# SCH_urmom_2025-01-09.net
KiCad netlist of a schematic drawn in EasyEDA
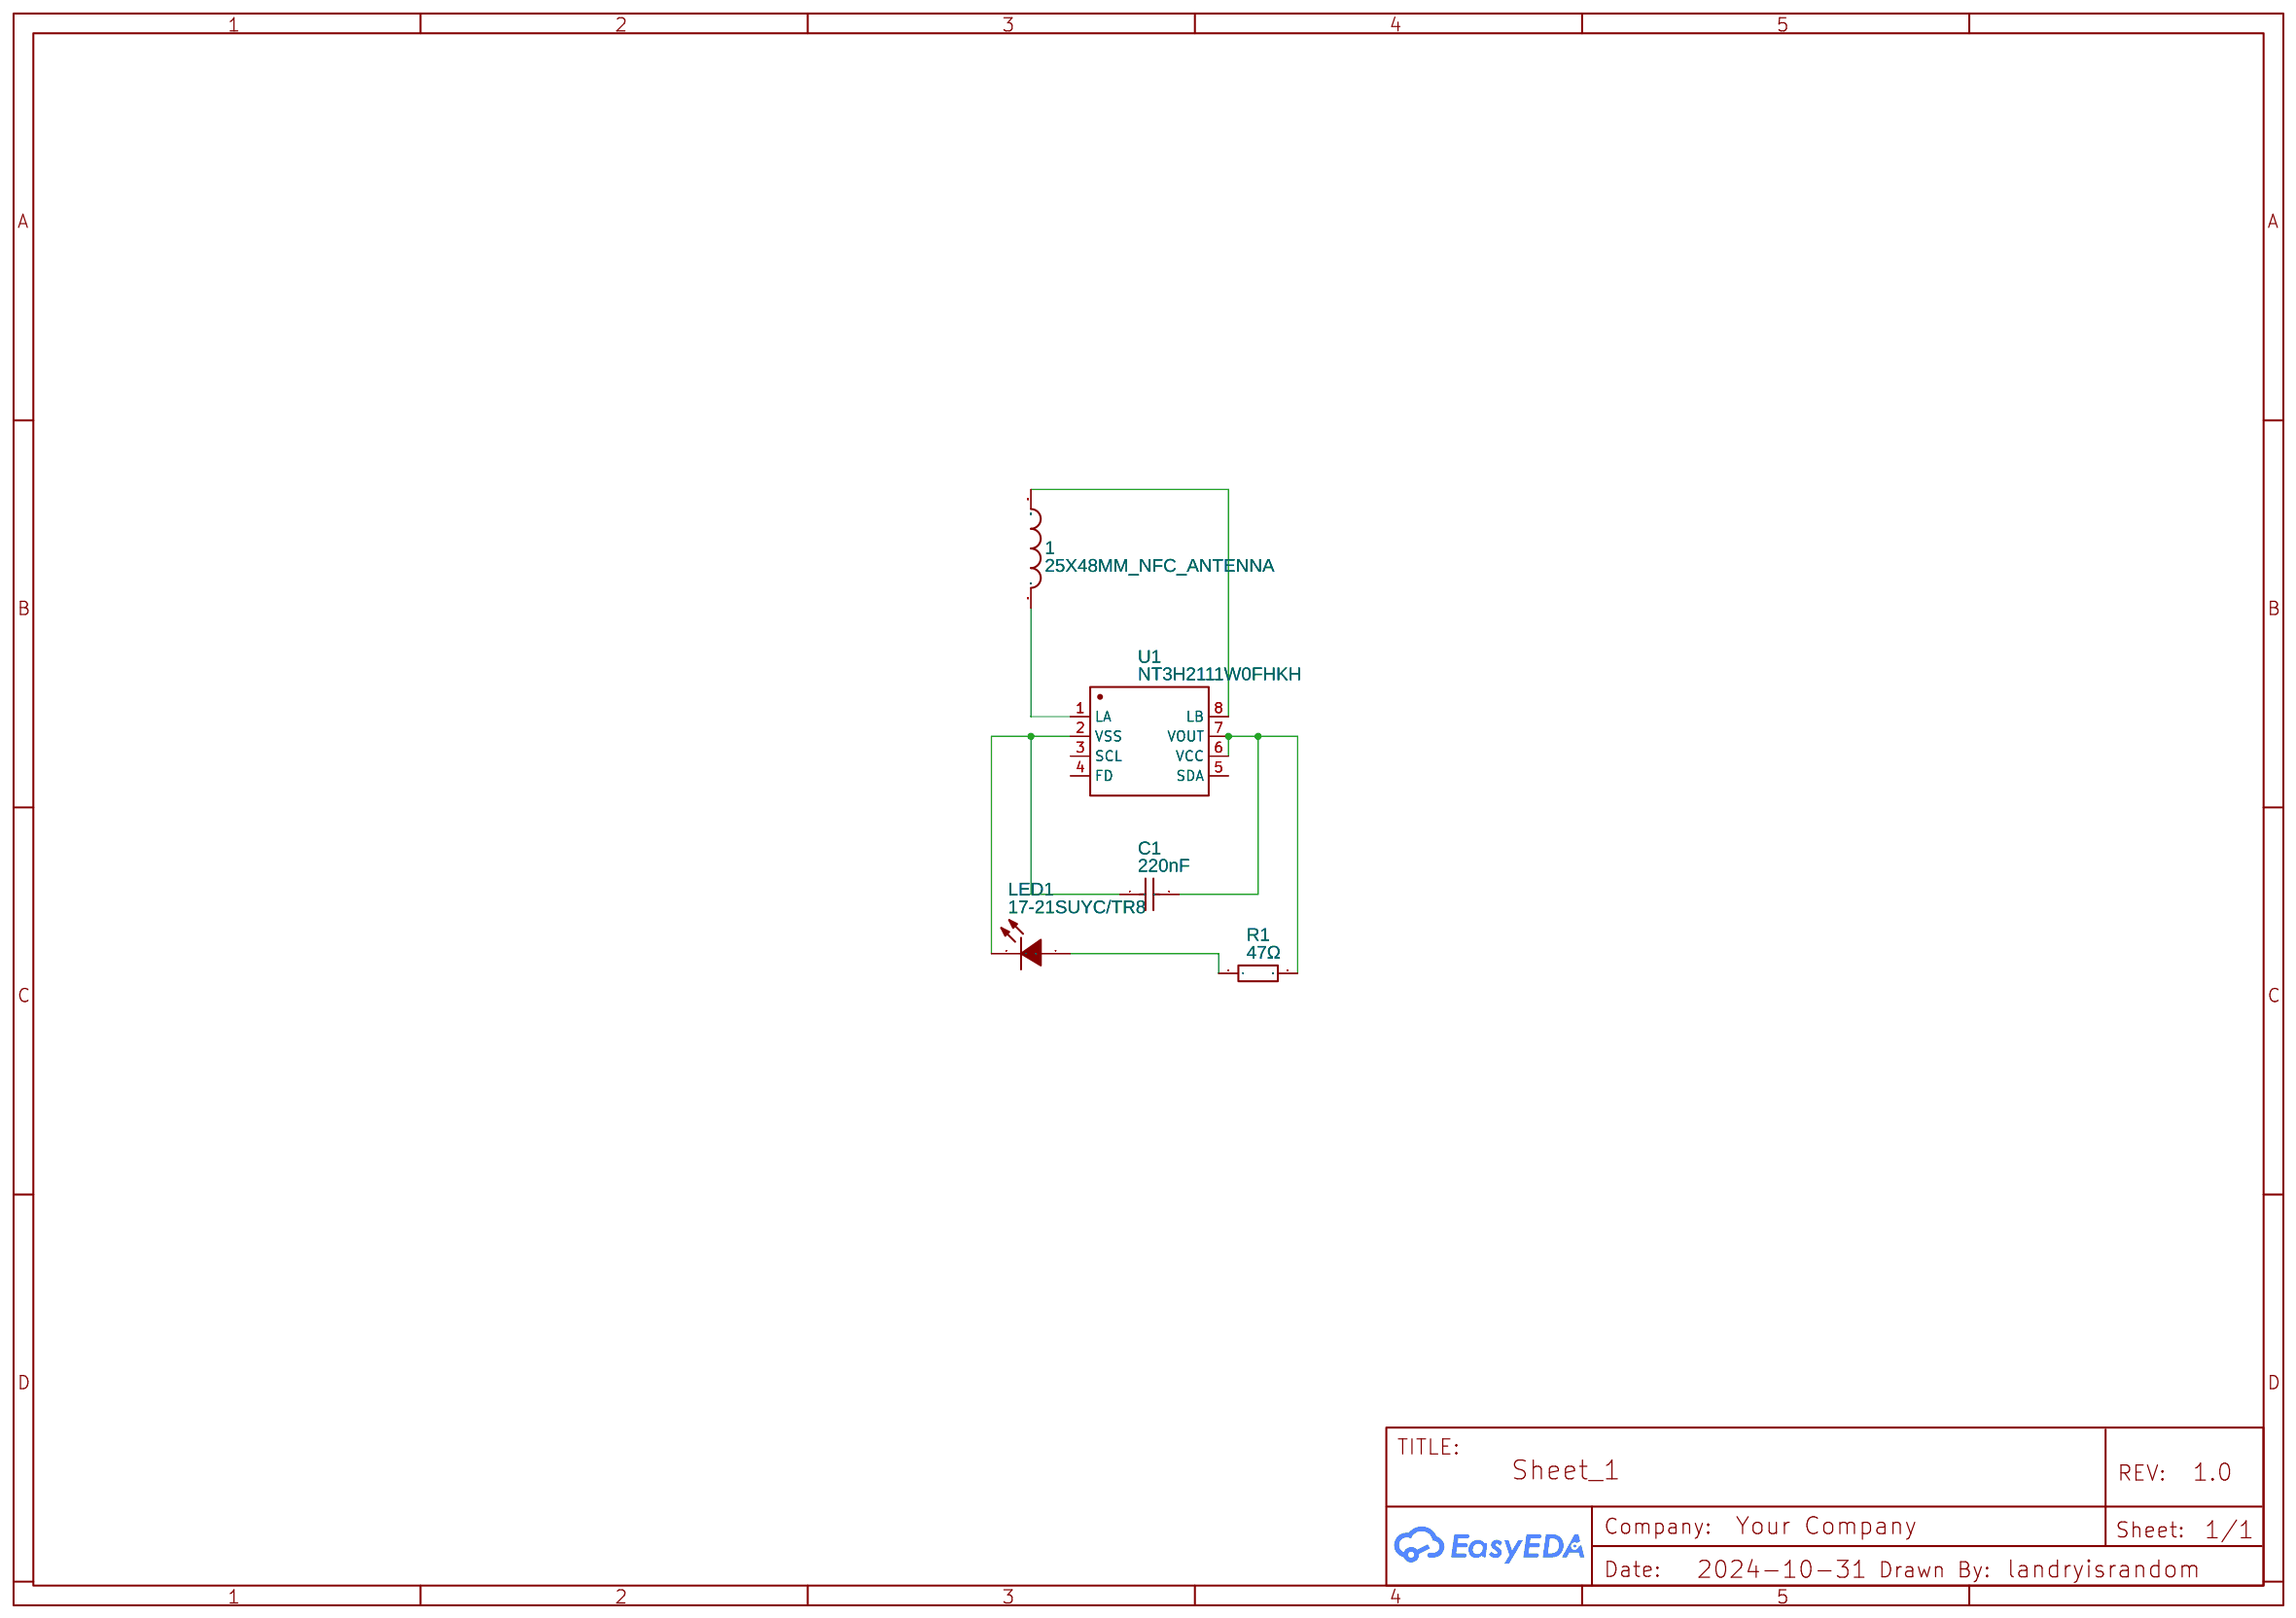
[diagram p0: schematic sheet]

(export (version "E")
  (design (tool "Eeschema 10.0.6"))
  (components
    (comp (ref "1") (value "25X48MM_NFC_ANTENNA") (libsource (lib "") (part "25X48MM_NFC_ANTENNA")))
    (comp (ref "C1")
      (value "220nF")
      (fields
        (field (name "Manufacturer Part") "CL10B224KA8NNNC")
        (field (name "Manufacturer") "SAMSUNG(三星)")
      )
      (libsource (lib "") (part "CL10B224KA8NNNC"))
    )
    (comp (ref "LED1")
      (value "17-21SUYC/TR8")
      (fields (field (name "Manufacturer Part") "KT-0805黄灯") (field (name "Manufacturer") "KENTO"))
      (libsource (lib "") (part "17-21SUYC/TR8"))
    )
    (comp (ref "R1")
      (value "47Ω")
      (fields
        (field (name "Manufacturer Part") "0603WAF470JT5E")
        (field (name "Manufacturer") "UNI-ROYAL(厚声)")
      )
      (libsource (lib "") (part "0603WAF470JT5E"))
    )
    (comp (ref "U1")
      (value "NT3H2111W0FHKH")
      (fields (field (name "Manufacturer") "NXP(恩智浦)"))
      (libsource (lib "") (part "NT3H2111W0FHKH"))
    )
  )
  (nets
    (net (code "1") (name "Net-(LED1-+)") (class "Default")
      (node (ref "LED1") (pin "1") (pinfunction "+_1") (pintype "unspecified"))
      (node (ref "R1") (pin "1") (pinfunction "1_1") (pintype "input"))
    )
    (net (code "2") (name "Net-(LED1--)") (class "Default")
      (node (ref "C1") (pin "1") (pinfunction "1_1") (pintype "input"))
      (node (ref "LED1") (pin "2") (pinfunction "-_2") (pintype "unspecified"))
      (node (ref "U1") (pin "2") (pinfunction "VSS_2") (pintype "unspecified"))
    )
    (net (code "3") (name "Net-(U1-LA)") (class "Default")
      (node (ref "1") (pin "P$2") (pinfunction "P$2_P$2") (pintype "bidirectional"))
      (node (ref "U1") (pin "1") (pinfunction "LA_1") (pintype "unspecified"))
    )
    (net (code "4") (name "Net-(U1-LB)") (class "Default")
      (node (ref "1") (pin "P$1") (pinfunction "P$1_P$1") (pintype "bidirectional"))
      (node (ref "U1") (pin "8") (pinfunction "LB_8") (pintype "unspecified"))
    )
    (net (code "5") (name "Net-(U1-VCC)") (class "Default")
      (node (ref "C1") (pin "2") (pinfunction "2_2") (pintype "input"))
      (node (ref "R1") (pin "2") (pinfunction "2_2") (pintype "input"))
      (node (ref "U1") (pin "6") (pinfunction "VCC_6") (pintype "unspecified"))
      (node (ref "U1") (pin "7") (pinfunction "VOUT_7") (pintype "unspecified"))
    )
    (net (code "6") (name "unconnected-(U1-FD-Pad4)") (class "Default")
      (node (ref "U1") (pin "4") (pinfunction "FD_4") (pintype "unspecified"))
    )
    (net (code "7") (name "unconnected-(U1-SCL-Pad3)") (class "Default")
      (node (ref "U1") (pin "3") (pinfunction "SCL_3") (pintype "unspecified"))
    )
    (net (code "8") (name "unconnected-(U1-SDA-Pad5)") (class "Default")
      (node (ref "U1") (pin "5") (pinfunction "SDA_5") (pintype "unspecified"))
    )
  )
)
